# 4H-RGBLight.net
KiCad netlist of a schematic drawn in EAGLE
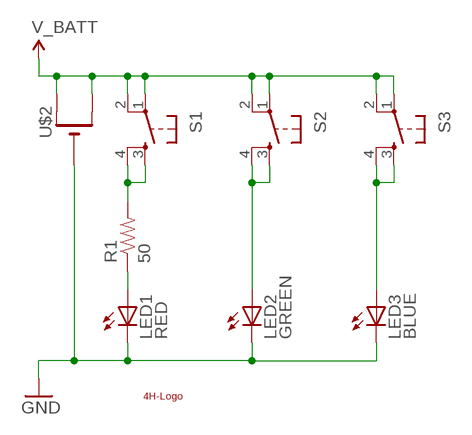
[diagram p0: schematic, sheet 1]

(export (version "E")
  (design (tool "Eeschema 10.0.6"))
  (components
    (comp (ref "LED1")
      (value "RED")
      (footprint "eagle-import:LED-OVAL")
      (libsource (lib "eagle-import") (part "LEDOVAL"))
    )
    (comp (ref "LED2")
      (value "GREEN")
      (footprint "eagle-import:LED-OVAL")
      (libsource (lib "eagle-import") (part "LEDOVAL"))
    )
    (comp (ref "LED3")
      (value "BLUE")
      (footprint "eagle-import:LED-OVAL")
      (libsource (lib "eagle-import") (part "LEDOVAL"))
    )
    (comp (ref "R1")
      (value "50")
      (footprint "eagle-import:AXIAL-0.3")
      (libsource (lib "eagle-import") (part "RESISTORAXIAL-0.3"))
    )
    (comp (ref "S1")
      (value "TAC_SWITCHPTH")
      (footprint "eagle-import:TACTILE-PTH")
      (libsource (lib "eagle-import") (part "TAC_SWITCHPTH"))
    )
    (comp (ref "S2")
      (value "TAC_SWITCHPTH")
      (footprint "eagle-import:TACTILE-PTH")
      (libsource (lib "eagle-import") (part "TAC_SWITCHPTH"))
    )
    (comp (ref "S3")
      (value "TAC_SWITCHPTH")
      (footprint "eagle-import:TACTILE-PTH")
      (libsource (lib "eagle-import") (part "TAC_SWITCHPTH"))
    )
    (comp (ref "U$2")
      (value "CR2032THM")
      (footprint "eagle-import:CR2032-THRU")
      (libsource (lib "eagle-import") (part "CR2032THM"))
    )
    (comp (ref "U$3")
      (value "4H-LOGO6")
      (footprint "eagle-import:4H_LOGO_6")
      (libsource (lib "eagle-import") (part "4H-LOGO6"))
    )
  )
  (nets
    (net (code "1") (name "GND") (class "Default")
      (node (ref "LED1") (pin "CATHODE") (pinfunction "C_CATHODE") (pintype "passive"))
      (node (ref "LED2") (pin "CATHODE") (pinfunction "C_CATHODE") (pintype "passive"))
      (node (ref "LED3") (pin "CATHODE") (pinfunction "C_CATHODE") (pintype "passive"))
      (node (ref "U$2") (pin "-") (pinfunction "-_-") (pintype "passive"))
    )
    (net (code "2") (name "Net-(LED1-A)") (class "Default")
      (node (ref "LED1") (pin "ANODE") (pinfunction "A_ANODE") (pintype "passive"))
      (node (ref "R1") (pin "P$1") (pinfunction "1_P$1") (pintype "passive"))
    )
    (net (code "3") (name "Net-(LED2-A)") (class "Default")
      (node (ref "LED2") (pin "ANODE") (pinfunction "A_ANODE") (pintype "passive"))
      (node (ref "S2") (pin "3") (pinfunction "3_3") (pintype "passive"))
      (node (ref "S2") (pin "4") (pinfunction "4_4") (pintype "passive"))
    )
    (net (code "4") (name "Net-(LED3-A)") (class "Default")
      (node (ref "LED3") (pin "ANODE") (pinfunction "A_ANODE") (pintype "passive"))
      (node (ref "S3") (pin "3") (pinfunction "3_3") (pintype "passive"))
      (node (ref "S3") (pin "4") (pinfunction "4_4") (pintype "passive"))
    )
    (net (code "5") (name "Net-(R1-2)") (class "Default")
      (node (ref "R1") (pin "P$2") (pinfunction "2_P$2") (pintype "passive"))
      (node (ref "S1") (pin "3") (pinfunction "3_3") (pintype "passive"))
      (node (ref "S1") (pin "4") (pinfunction "4_4") (pintype "passive"))
    )
    (net (code "6") (name "V_BATT") (class "Default")
      (node (ref "S1") (pin "1") (pinfunction "1_1") (pintype "passive"))
      (node (ref "S1") (pin "2") (pinfunction "2_2") (pintype "passive"))
      (node (ref "S2") (pin "1") (pinfunction "1_1") (pintype "passive"))
      (node (ref "S2") (pin "2") (pinfunction "2_2") (pintype "passive"))
      (node (ref "S3") (pin "1") (pinfunction "1_1") (pintype "passive"))
      (node (ref "S3") (pin "2") (pinfunction "2_2") (pintype "passive"))
      (node (ref "U$2") (pin "+1") (pinfunction "+_+1") (pintype "passive"))
      (node (ref "U$2") (pin "+2") (pinfunction "+1_+2") (pintype "passive"))
    )
  )
)
